# hdmi.net
KiCad netlist of a schematic drawn in Altium Designer
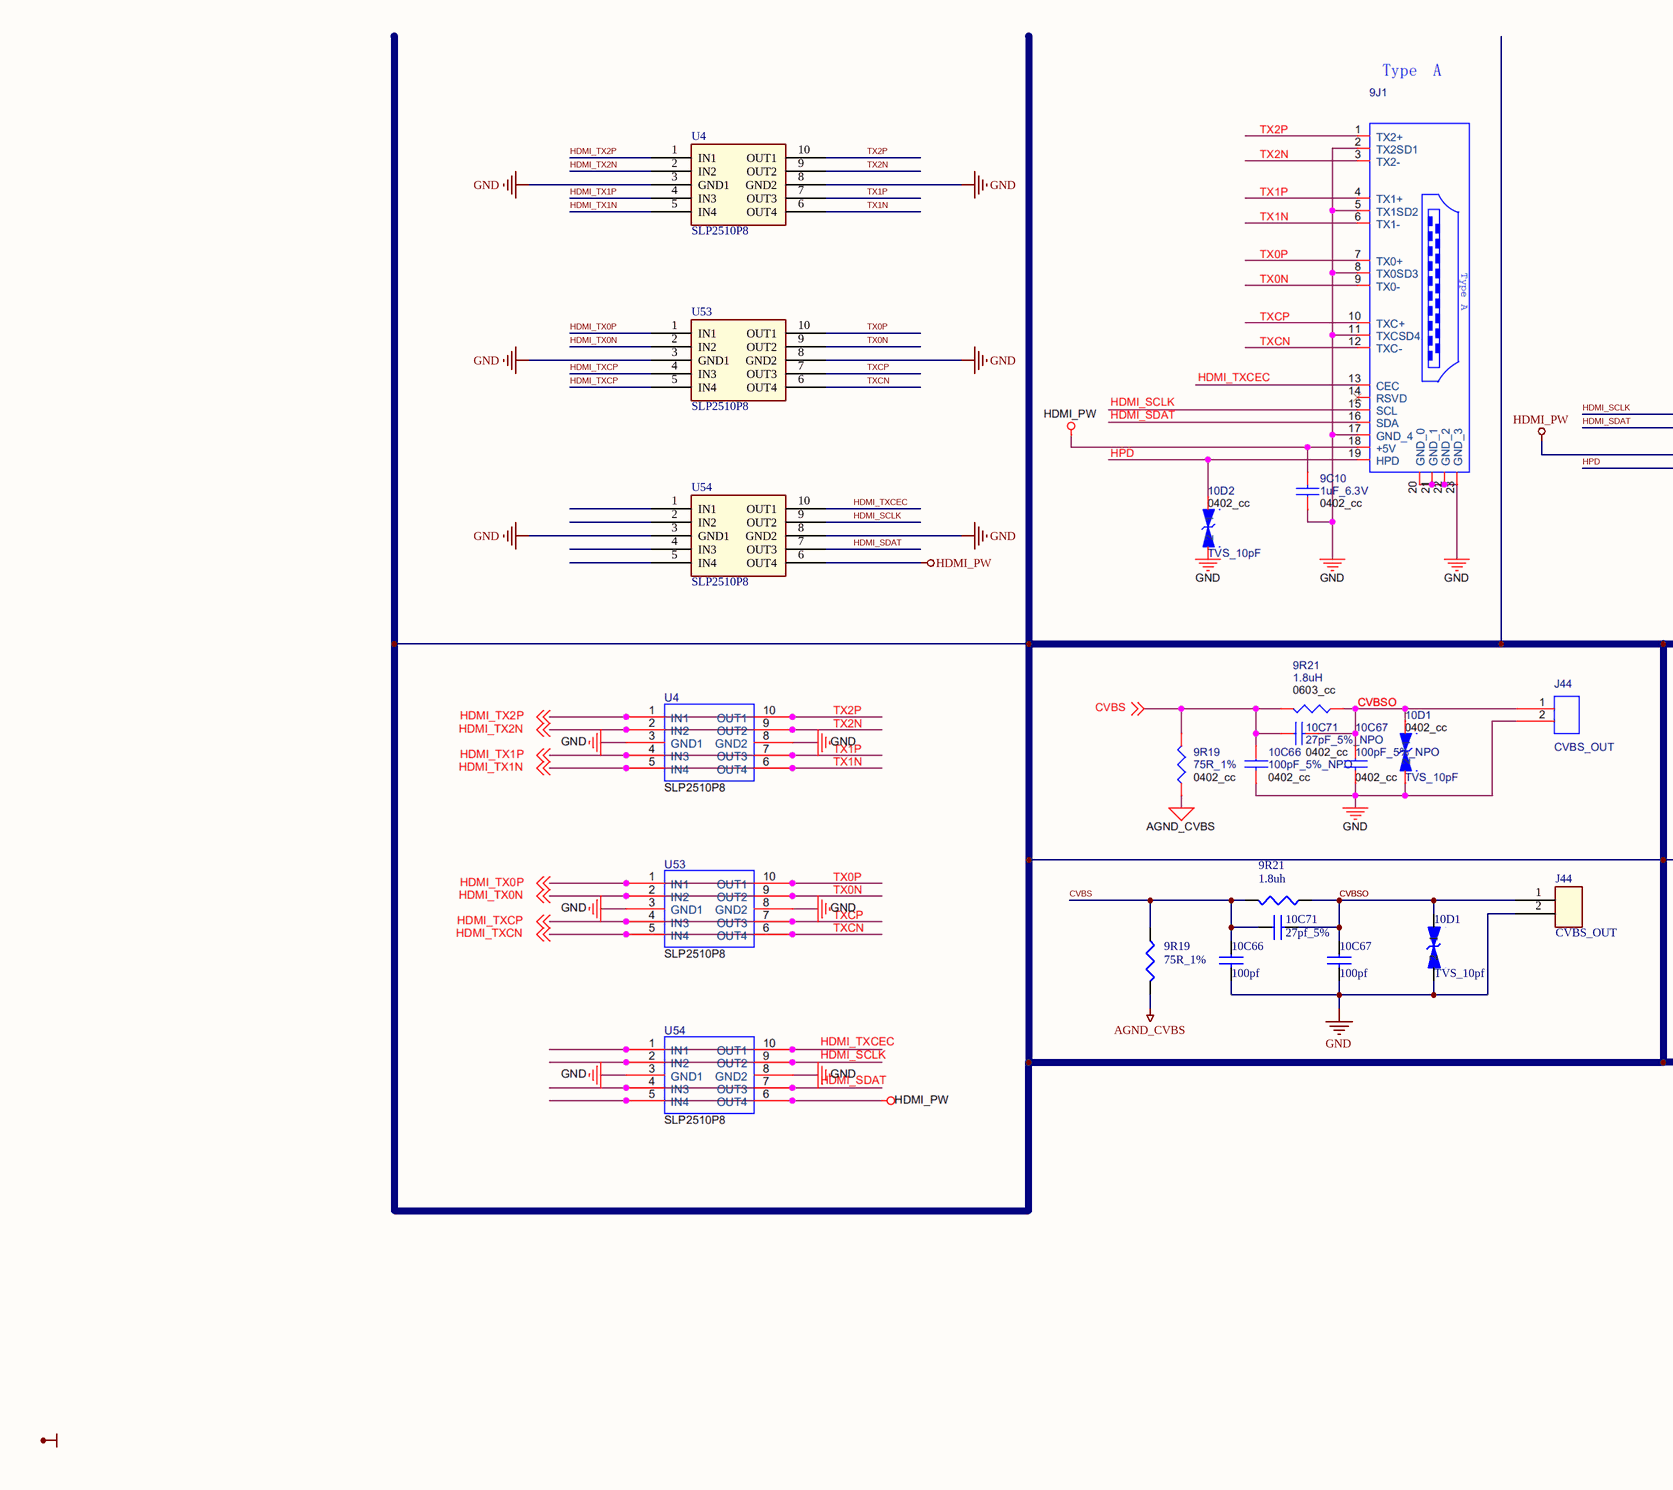
[diagram p0: hdmi.SchDoc, left]
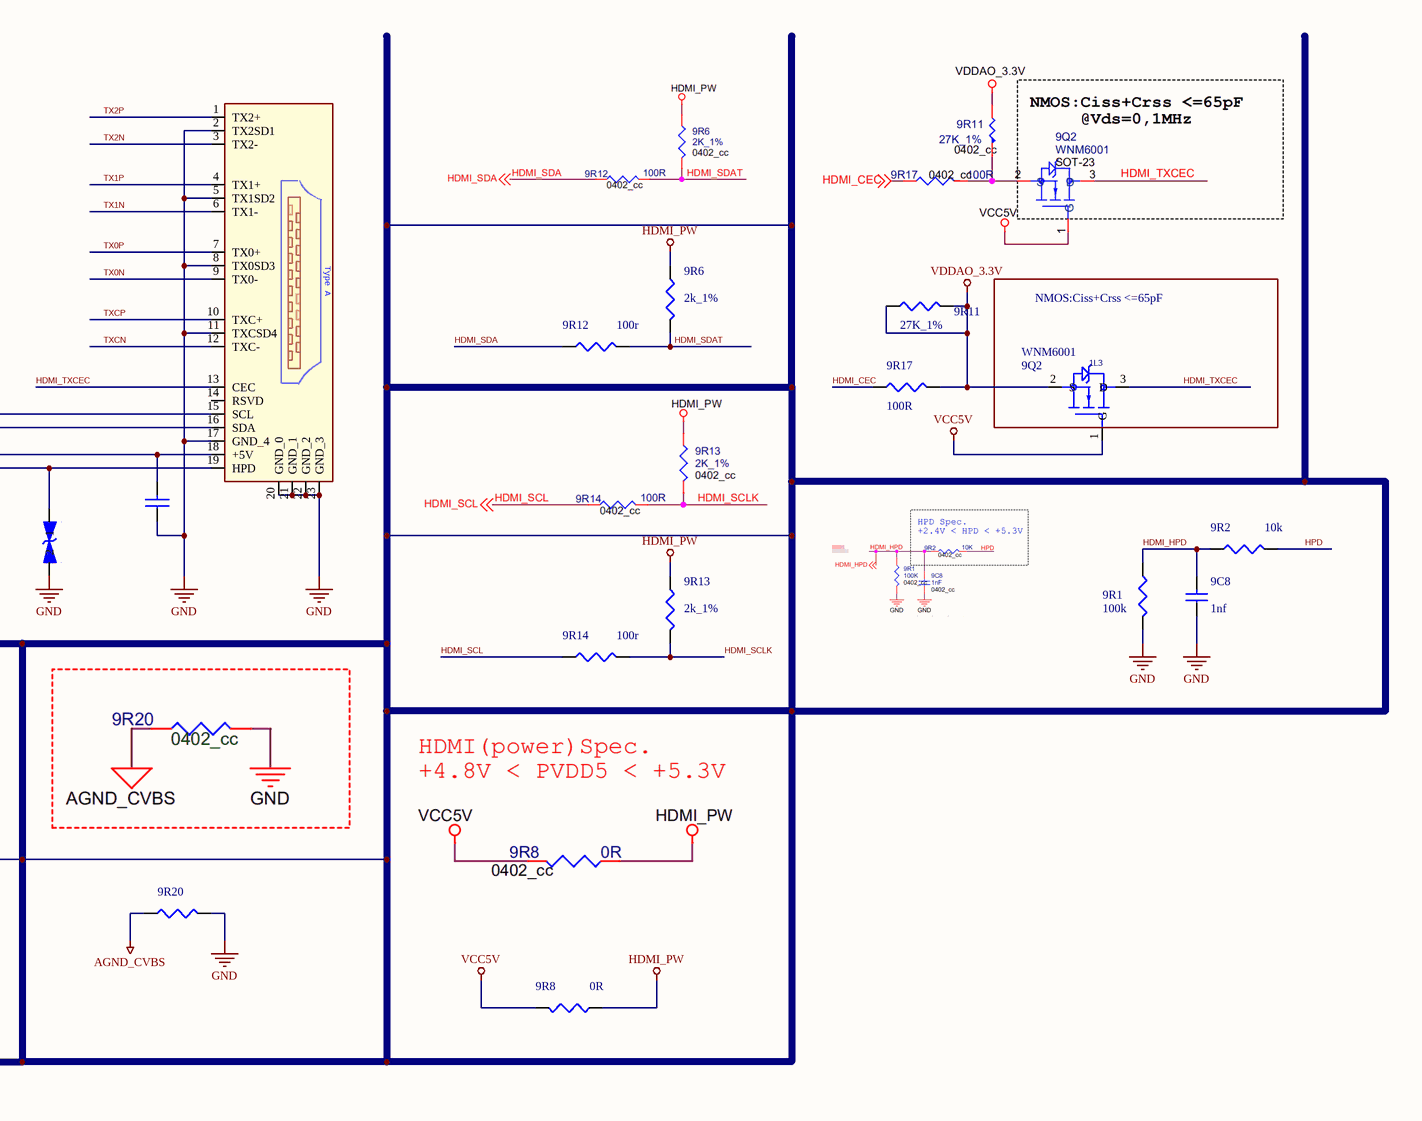
[diagram p1: hdmi.SchDoc, right]

(export (version "E")
  (design (tool "Eeschema 10.0.6"))
  (components
    (comp (ref "9C8") (value "1nf") (footprint "0603C") (libsource (lib "*") (part "capnp")))
    (comp (ref "9C10") (value "~") (libsource (lib "*") (part "CAP NP_6")))
    (comp (ref "9J1") (value "~") (libsource (lib "*") (part "J-HDMI-TYPE-A-19P_1")))
    (comp (ref "9Q2")
      (value "WNM6001")
      (description "SOT-23")
      (fields (field (name "J102") "1L3"))
      (libsource (lib "*") (part "Mosfetp_4"))
    )
    (comp (ref "9R1") (value "100k") (libsource (lib "*") (part "RESISTOR")))
    (comp (ref "9R2") (value "10k") (libsource (lib "*") (part "RESISTOR")))
    (comp (ref "9R6") (value "2k_1%") (libsource (lib "*") (part "RESISTOR")))
    (comp (ref "9R8") (value "0R") (libsource (lib "*") (part "RESISTOR")))
    (comp (ref "9R11") (value "27K_1%") (libsource (lib "*") (part "R")))
    (comp (ref "9R12") (value "100r") (libsource (lib "*") (part "RESISTOR")))
    (comp (ref "9R13") (value "2k_1%") (libsource (lib "*") (part "RESISTOR")))
    (comp (ref "9R14") (value "100r") (libsource (lib "*") (part "RESISTOR")))
    (comp (ref "9R17") (value "100R") (libsource (lib "*") (part "R")))
    (comp (ref "9R19") (value "75R_1%") (libsource (lib "*") (part "RESISTOR_3")))
    (comp (ref "9R20") (value "~") (libsource (lib "*") (part "RESISTOR")))
    (comp (ref "9R21") (value "1.8uh") (libsource (lib "*") (part "RESISTOR_3")))
    (comp (ref "10C66") (value "100pf") (libsource (lib "*") (part "CAP NP_6")))
    (comp (ref "10C67") (value "100pf") (libsource (lib "*") (part "CAP NP_6")))
    (comp (ref "10C71") (value "27pf_5%") (libsource (lib "*") (part "CAP NP_6")))
    (comp (ref "10D1") (value "TVS_10pf") (libsource (lib "*") (part "TVS DIODE")))
    (comp (ref "10D2") (value "~") (libsource (lib "*") (part "TVS DIODE")))
    (comp (ref "J44") (value "CVBS_OUT") (libsource (lib "*") (part "CON2")))
    (comp (ref "U4") (value "SLP2510P8") (libsource (lib "*") (part "rRClamp0524P")))
    (comp (ref "U53") (value "SLP2510P8") (libsource (lib "*") (part "rRClamp0524P")))
    (comp (ref "U54") (value "SLP2510P8") (libsource (lib "*") (part "rRClamp0524P")))
  )
  (nets
    (net (code "1") (name "/CVBS") (class "Default")
      (node (ref "10C66") (pin "1") (pinfunction "1_1") (pintype "passive"))
      (node (ref "10C71") (pin "1") (pinfunction "1_1") (pintype "passive"))
      (node (ref "9R19") (pin "1") (pinfunction "1_1") (pintype "passive"))
      (node (ref "9R21") (pin "2") (pinfunction "2_2") (pintype "passive"))
    )
    (net (code "2") (name "/CVBSO") (class "Default")
      (node (ref "10C67") (pin "1") (pinfunction "1_1") (pintype "passive"))
      (node (ref "10C71") (pin "2") (pinfunction "2_2") (pintype "passive"))
      (node (ref "10D1") (pin "1") (pinfunction "1_1") (pintype "passive"))
      (node (ref "9R21") (pin "1") (pinfunction "1_1") (pintype "passive"))
      (node (ref "J44") (pin "1") (pinfunction "1_1") (pintype "passive"))
    )
    (net (code "3") (name "/HDMI_CEC") (class "Default")
      (node (ref "9R17") (pin "2") (pinfunction "2_2") (pintype "passive"))
    )
    (net (code "4") (name "/HDMI_HPD") (class "Default")
      (node (ref "9C8") (pin "2") (pinfunction "2_2") (pintype "passive"))
      (node (ref "9R1") (pin "1") (pinfunction "1_1") (pintype "passive"))
      (node (ref "9R2") (pin "1") (pinfunction "1_1") (pintype "passive"))
    )
    (net (code "5") (name "/HDMI_SCL") (class "Default")
      (node (ref "9R14") (pin "1") (pinfunction "1_1") (pintype "passive"))
    )
    (net (code "6") (name "/HDMI_SCLK") (class "Default")
      (node (ref "9J1") (pin "15") (pinfunction "SCL_15") (pintype "passive"))
      (node (ref "9R13") (pin "2") (pinfunction "2_2") (pintype "passive"))
      (node (ref "9R14") (pin "2") (pinfunction "2_2") (pintype "passive"))
      (node (ref "U54") (pin "9") (pinfunction "OUT2_9") (pintype "passive"))
    )
    (net (code "7") (name "/HDMI_SDA") (class "Default")
      (node (ref "9R12") (pin "1") (pinfunction "1_1") (pintype "passive"))
    )
    (net (code "8") (name "/HDMI_SDAT") (class "Default")
      (node (ref "9J1") (pin "16") (pinfunction "SDA_16") (pintype "passive"))
      (node (ref "9R12") (pin "2") (pinfunction "2_2") (pintype "passive"))
      (node (ref "9R6") (pin "2") (pinfunction "2_2") (pintype "passive"))
      (node (ref "U54") (pin "7") (pinfunction "OUT3_7") (pintype "passive"))
    )
    (net (code "9") (name "/HDMI_TX0N") (class "Default")
      (node (ref "U53") (pin "2") (pinfunction "IN2_2") (pintype "passive"))
    )
    (net (code "10") (name "/HDMI_TX0P") (class "Default")
      (node (ref "U53") (pin "1") (pinfunction "IN1_1") (pintype "passive"))
    )
    (net (code "11") (name "/HDMI_TX1N") (class "Default")
      (node (ref "U4") (pin "5") (pinfunction "IN4_5") (pintype "passive"))
    )
    (net (code "12") (name "/HDMI_TX1P") (class "Default")
      (node (ref "U4") (pin "4") (pinfunction "IN3_4") (pintype "passive"))
    )
    (net (code "13") (name "/HDMI_TX2N") (class "Default")
      (node (ref "U4") (pin "2") (pinfunction "IN2_2") (pintype "passive"))
    )
    (net (code "14") (name "/HDMI_TX2P") (class "Default")
      (node (ref "U4") (pin "1") (pinfunction "IN1_1") (pintype "passive"))
    )
    (net (code "15") (name "/HDMI_TXCEC") (class "Default")
      (node (ref "9J1") (pin "13") (pinfunction "CEC_13") (pintype "passive"))
      (node (ref "9Q2") (pin "3") (pinfunction "D_3") (pintype "passive"))
      (node (ref "U54") (pin "10") (pinfunction "OUT1_10") (pintype "passive"))
    )
    (net (code "16") (name "/HDMI_TXCP") (class "Default")
      (node (ref "U53") (pin "4") (pinfunction "IN3_4") (pintype "passive"))
      (node (ref "U53") (pin "5") (pinfunction "IN4_5") (pintype "passive"))
    )
    (net (code "17") (name "/HPD") (class "Default")
      (node (ref "10D2") (pin "1") (pinfunction "1_1") (pintype "passive"))
      (node (ref "9J1") (pin "19") (pinfunction "HPD_19") (pintype "passive"))
      (node (ref "9R2") (pin "2") (pinfunction "2_2") (pintype "passive"))
    )
    (net (code "18") (name "/TX0N") (class "Default")
      (node (ref "9J1") (pin "9") (pinfunction "TX0-_9") (pintype "passive"))
      (node (ref "U53") (pin "9") (pinfunction "OUT2_9") (pintype "passive"))
    )
    (net (code "19") (name "/TX0P") (class "Default")
      (node (ref "9J1") (pin "7") (pinfunction "TX0+_7") (pintype "passive"))
      (node (ref "U53") (pin "10") (pinfunction "OUT1_10") (pintype "passive"))
    )
    (net (code "20") (name "/TX1N") (class "Default")
      (node (ref "9J1") (pin "6") (pinfunction "TX1-_6") (pintype "passive"))
      (node (ref "U4") (pin "6") (pinfunction "OUT4_6") (pintype "passive"))
    )
    (net (code "21") (name "/TX1P") (class "Default")
      (node (ref "9J1") (pin "4") (pinfunction "TX1+_4") (pintype "passive"))
      (node (ref "U4") (pin "7") (pinfunction "OUT3_7") (pintype "passive"))
    )
    (net (code "22") (name "/TX2N") (class "Default")
      (node (ref "9J1") (pin "3") (pinfunction "TX2-_3") (pintype "passive"))
      (node (ref "U4") (pin "9") (pinfunction "OUT2_9") (pintype "passive"))
    )
    (net (code "23") (name "/TX2P") (class "Default")
      (node (ref "9J1") (pin "1") (pinfunction "TX2+_1") (pintype "passive"))
      (node (ref "U4") (pin "10") (pinfunction "OUT1_10") (pintype "passive"))
    )
    (net (code "24") (name "/TXCN") (class "Default")
      (node (ref "9J1") (pin "12") (pinfunction "TXC-_12") (pintype "passive"))
      (node (ref "U53") (pin "6") (pinfunction "OUT4_6") (pintype "passive"))
    )
    (net (code "25") (name "/TXCP") (class "Default")
      (node (ref "9J1") (pin "10") (pinfunction "TXC+_10") (pintype "passive"))
      (node (ref "U53") (pin "7") (pinfunction "OUT3_7") (pintype "passive"))
    )
    (net (code "27") (name "AGND_CVBS") (class "Default")
      (node (ref "9R19") (pin "2") (pinfunction "2_2") (pintype "passive"))
      (node (ref "9R20") (pin "1") (pinfunction "1_1") (pintype "passive"))
    )
    (net (code "28") (name "GND") (class "Default")
      (node (ref "10C66") (pin "2") (pinfunction "2_2") (pintype "passive"))
      (node (ref "10C67") (pin "2") (pinfunction "2_2") (pintype "passive"))
      (node (ref "10D1") (pin "2") (pinfunction "2_2") (pintype "passive"))
      (node (ref "10D2") (pin "2") (pinfunction "2_2") (pintype "passive"))
      (node (ref "9C10") (pin "1") (pinfunction "1_1") (pintype "passive"))
      (node (ref "9C8") (pin "1") (pinfunction "1_1") (pintype "passive"))
      (node (ref "9J1") (pin "11") (pinfunction "TXCSD4_11") (pintype "passive"))
      (node (ref "9J1") (pin "17") (pinfunction "GND_4_17") (pintype "passive"))
      (node (ref "9J1") (pin "2") (pinfunction "TX2SD1_2") (pintype "passive"))
      (node (ref "9J1") (pin "20") (pinfunction "GND_0_20") (pintype "passive"))
      (node (ref "9J1") (pin "21") (pinfunction "GND_1_21") (pintype "passive"))
      (node (ref "9J1") (pin "22") (pinfunction "GND_2_22") (pintype "passive"))
      (node (ref "9J1") (pin "23") (pinfunction "GND_3_23") (pintype "passive"))
      (node (ref "9J1") (pin "5") (pinfunction "TX1SD2_5") (pintype "passive"))
      (node (ref "9J1") (pin "8") (pinfunction "TX0SD3_8") (pintype "passive"))
      (node (ref "9R1") (pin "2") (pinfunction "2_2") (pintype "passive"))
      (node (ref "9R20") (pin "2") (pinfunction "2_2") (pintype "passive"))
      (node (ref "J44") (pin "2") (pinfunction "2_2") (pintype "passive"))
      (node (ref "U4") (pin "3") (pinfunction "GND1_3") (pintype "passive"))
      (node (ref "U4") (pin "8") (pinfunction "GND2_8") (pintype "passive"))
      (node (ref "U53") (pin "3") (pinfunction "GND1_3") (pintype "passive"))
      (node (ref "U53") (pin "8") (pinfunction "GND2_8") (pintype "passive"))
      (node (ref "U54") (pin "3") (pinfunction "GND1_3") (pintype "passive"))
      (node (ref "U54") (pin "8") (pinfunction "GND2_8") (pintype "passive"))
    )
    (net (code "29") (name "HDMI_PW") (class "Default")
      (node (ref "9C10") (pin "2") (pinfunction "2_2") (pintype "passive"))
      (node (ref "9J1") (pin "18") (pinfunction "+5V_18") (pintype "passive"))
      (node (ref "9R13") (pin "1") (pinfunction "1_1") (pintype "passive"))
      (node (ref "9R6") (pin "1") (pinfunction "1_1") (pintype "passive"))
      (node (ref "9R8") (pin "1") (pinfunction "1_1") (pintype "passive"))
      (node (ref "U54") (pin "6") (pinfunction "OUT4_6") (pintype "passive"))
    )
    (net (code "30") (name "VCC5V") (class "Default")
      (node (ref "9Q2") (pin "1") (pinfunction "G_1") (pintype "passive"))
      (node (ref "9R8") (pin "2") (pinfunction "2_2") (pintype "passive"))
    )
    (net (code "31") (name "VDDAO_3.3V") (class "Default")
      (node (ref "9Q2") (pin "2") (pinfunction "S_2") (pintype "passive"))
      (node (ref "9R11") (pin "1") (pinfunction "1_1") (pintype "passive"))
      (node (ref "9R11") (pin "2") (pinfunction "2_2") (pintype "passive"))
      (node (ref "9R17") (pin "1") (pinfunction "1_1") (pintype "passive"))
    )
    (net (code "32") (name "unconnected-(9J1-RSVD-Pad14)") (class "Default")
      (node (ref "9J1") (pin "14") (pinfunction "RSVD_14") (pintype "passive"))
    )
    (net (code "33") (name "unconnected-(U54-IN1-Pad1)") (class "Default")
      (node (ref "U54") (pin "1") (pinfunction "IN1_1") (pintype "passive"))
    )
    (net (code "34") (name "unconnected-(U54-IN2-Pad2)") (class "Default")
      (node (ref "U54") (pin "2") (pinfunction "IN2_2") (pintype "passive"))
    )
    (net (code "35") (name "unconnected-(U54-IN3-Pad4)") (class "Default")
      (node (ref "U54") (pin "4") (pinfunction "IN3_4") (pintype "passive"))
    )
    (net (code "36") (name "unconnected-(U54-IN4-Pad5)") (class "Default")
      (node (ref "U54") (pin "5") (pinfunction "IN4_5") (pintype "passive"))
    )
  )
)
